# DRV8873.net
KiCad netlist of a schematic drawn in Altium Designer
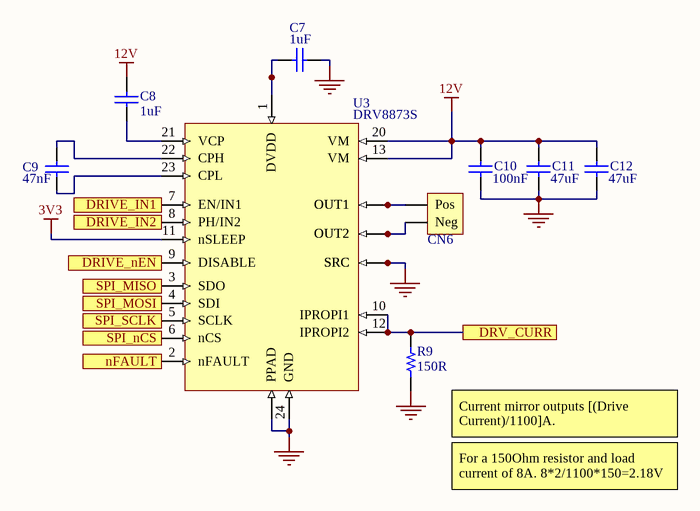
[diagram p0: DRV8873.SchDoc]

(export (version "E")
  (design (tool "Eeschema 10.0.6"))
  (components
    (comp (ref "C7")
      (value "1uF")
      (footprint "0402")
      (fields (field (name "Comment") "Cap") (field (name "PUBLISHER") "Altium Limited"))
      (libsource (lib "Parts") (part "Cap"))
    )
    (comp (ref "C8")
      (value "1uF")
      (footprint "0402")
      (fields (field (name "Comment") "Cap") (field (name "PUBLISHER") "Altium Limited"))
      (libsource (lib "Parts") (part "Cap"))
    )
    (comp (ref "C9")
      (value "47nF")
      (footprint "0402")
      (fields (field (name "Comment") "Cap") (field (name "PUBLISHER") "Altium Limited"))
      (libsource (lib "Parts") (part "Cap"))
    )
    (comp (ref "C10")
      (value "100nF")
      (footprint "0402")
      (fields (field (name "Comment") "Cap") (field (name "PUBLISHER") "Altium Limited"))
      (libsource (lib "Parts") (part "Cap"))
    )
    (comp (ref "C11")
      (value "47uF")
      (footprint "1206")
      (fields (field (name "Comment") "Cap") (field (name "PUBLISHER") "Altium Limited"))
      (libsource (lib "Parts") (part "Cap"))
    )
    (comp (ref "C12")
      (value "47uF")
      (footprint "1206")
      (fields (field (name "Comment") "Cap") (field (name "PUBLISHER") "Altium Limited"))
      (libsource (lib "Parts") (part "Cap"))
    )
    (comp (ref "CN6")
      (value "JST_Leads_In")
      (footprint "Power_Leads")
      (libsource (lib "Parts") (part "JST_Leads_In"))
    )
    (comp (ref "R9")
      (value "150R")
      (footprint "0805 - duplicate")
      (libsource (lib "Parts") (part "Resistor"))
    )
    (comp (ref "U3") (value "DRV8873S") (footprint "HTSSOP24") (libsource (lib "Parts") (part "DRV8873S")))
  )
  (nets
    (net (code "1") (name "/DRIVE_IN1") (class "Default")
      (node (ref "U3") (pin "7") (pinfunction "EN/IN1_7") (pintype "input"))
    )
    (net (code "2") (name "/DRIVE_IN2") (class "Default")
      (node (ref "U3") (pin "8") (pinfunction "PH/IN2_8") (pintype "input"))
    )
    (net (code "3") (name "/DRIVE_nEN") (class "Default")
      (node (ref "U3") (pin "9") (pinfunction "DISABLE_9") (pintype "input"))
    )
    (net (code "4") (name "/DRV_CURR") (class "Default")
      (node (ref "R9") (pin "2") (pinfunction "2_2") (pintype "passive"))
      (node (ref "U3") (pin "10") (pinfunction "IPROPI1_10") (pintype "input"))
      (node (ref "U3") (pin "12") (pinfunction "IPROPI2_12") (pintype "input"))
    )
    (net (code "5") (name "/SPI_MISO") (class "Default")
      (node (ref "U3") (pin "3") (pinfunction "SDO_3") (pintype "input"))
    )
    (net (code "6") (name "/SPI_MOSI") (class "Default")
      (node (ref "U3") (pin "4") (pinfunction "SDI_4") (pintype "input"))
    )
    (net (code "7") (name "/SPI_SCLK") (class "Default")
      (node (ref "U3") (pin "5") (pinfunction "SCLK_5") (pintype "input"))
    )
    (net (code "8") (name "/SPI_nCS") (class "Default")
      (node (ref "U3") (pin "6") (pinfunction "nCS_6") (pintype "input"))
    )
    (net (code "9") (name "/nFAULT") (class "Default")
      (node (ref "U3") (pin "2") (pinfunction "nFAULT_2") (pintype "input"))
    )
    (net (code "10") (name "3V3") (class "Default")
      (node (ref "U3") (pin "11") (pinfunction "nSLEEP_11") (pintype "input"))
    )
    (net (code "11") (name "12V") (class "Default")
      (node (ref "C10") (pin "2") (pinfunction "2_2") (pintype "passive"))
      (node (ref "C11") (pin "2") (pinfunction "2_2") (pintype "passive"))
      (node (ref "C12") (pin "2") (pinfunction "2_2") (pintype "passive"))
      (node (ref "C8") (pin "2") (pinfunction "2_2") (pintype "passive"))
      (node (ref "U3") (pin "13") (pinfunction "VM_13") (pintype "input"))
      (node (ref "U3") (pin "20") (pinfunction "VM_20") (pintype "input"))
    )
    (net (code "12") (name "GND") (class "Default")
      (node (ref "C10") (pin "1") (pinfunction "1_1") (pintype "passive"))
      (node (ref "C11") (pin "1") (pinfunction "1_1") (pintype "passive"))
      (node (ref "C12") (pin "1") (pinfunction "1_1") (pintype "passive"))
      (node (ref "C7") (pin "2") (pinfunction "2_2") (pintype "passive"))
      (node (ref "R9") (pin "1") (pinfunction "1_1") (pintype "passive"))
      (node (ref "U3") (pin "16") (pinfunction "SRC_16") (pintype "input"))
      (node (ref "U3") (pin "17") (pinfunction "SRC_17") (pintype "input"))
      (node (ref "U3") (pin "24") (pinfunction "GND_24") (pintype "input"))
      (node (ref "U3") (pin "THERM") (pinfunction "PPAD_THERM") (pintype "input"))
    )
    (net (code "13") (name "Net-(CN6-Neg)") (class "Default")
      (node (ref "CN6") (pin "K") (pinfunction "Neg_K") (pintype "passive"))
      (node (ref "U3") (pin "14") (pinfunction "OUT2_14") (pintype "input"))
      (node (ref "U3") (pin "15") (pinfunction "OUT2_15") (pintype "input"))
    )
    (net (code "14") (name "Net-(CN6-Pos)") (class "Default")
      (node (ref "CN6") (pin "A") (pinfunction "Pos_A") (pintype "passive"))
      (node (ref "U3") (pin "18") (pinfunction "OUT1_18") (pintype "input"))
      (node (ref "U3") (pin "19") (pinfunction "OUT1_19") (pintype "input"))
    )
    (net (code "15") (name "Net-(U3-CPH)") (class "Default")
      (node (ref "C9") (pin "2") (pinfunction "2_2") (pintype "passive"))
      (node (ref "U3") (pin "22") (pinfunction "CPH_22") (pintype "input"))
    )
    (net (code "16") (name "Net-(U3-CPL)") (class "Default")
      (node (ref "C9") (pin "1") (pinfunction "1_1") (pintype "passive"))
      (node (ref "U3") (pin "23") (pinfunction "CPL_23") (pintype "input"))
    )
    (net (code "17") (name "Net-(U3-DVDD)") (class "Default")
      (node (ref "C7") (pin "1") (pinfunction "1_1") (pintype "passive"))
      (node (ref "U3") (pin "1") (pinfunction "DVDD_1") (pintype "input"))
    )
    (net (code "18") (name "Net-(U3-VCP)") (class "Default")
      (node (ref "C8") (pin "1") (pinfunction "1_1") (pintype "passive"))
      (node (ref "U3") (pin "21") (pinfunction "VCP_21") (pintype "input"))
    )
  )
)
